# IR_LED.net
KiCad netlist of a schematic drawn in EAGLE
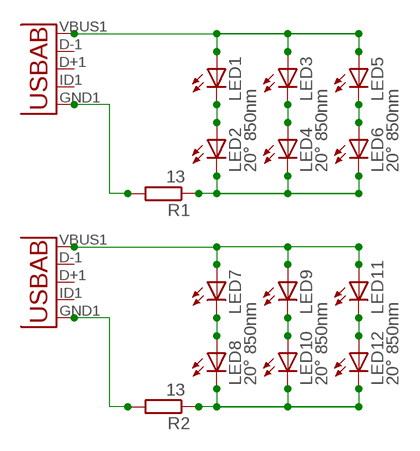
[diagram p0: schematic, sheet 1]

(export (version "E")
  (design (tool "Eeschema 10.0.6"))
  (components
    (comp (ref "LED1")
      (value "LED5MM")
      (footprint "eagle-import:LED5MM")
      (libsource (lib "eagle-import") (part "LED5MM"))
    )
    (comp (ref "LED2")
      (value "20° 850nm")
      (footprint "eagle-import:LED5MM")
      (libsource (lib "eagle-import") (part "LED5MM"))
    )
    (comp (ref "LED3")
      (value "LED5MM")
      (footprint "eagle-import:LED5MM")
      (libsource (lib "eagle-import") (part "LED5MM"))
    )
    (comp (ref "LED4")
      (value "20° 850nm")
      (footprint "eagle-import:LED5MM")
      (libsource (lib "eagle-import") (part "LED5MM"))
    )
    (comp (ref "LED5")
      (value "LED5MM")
      (footprint "eagle-import:LED5MM")
      (libsource (lib "eagle-import") (part "LED5MM"))
    )
    (comp (ref "LED6")
      (value "20° 850nm")
      (footprint "eagle-import:LED5MM")
      (libsource (lib "eagle-import") (part "LED5MM"))
    )
    (comp (ref "LED7")
      (value "LED5MM")
      (footprint "eagle-import:LED5MM")
      (libsource (lib "eagle-import") (part "LED5MM"))
    )
    (comp (ref "LED8")
      (value "20° 850nm")
      (footprint "eagle-import:LED5MM")
      (libsource (lib "eagle-import") (part "LED5MM"))
    )
    (comp (ref "LED9")
      (value "LED5MM")
      (footprint "eagle-import:LED5MM")
      (libsource (lib "eagle-import") (part "LED5MM"))
    )
    (comp (ref "LED10")
      (value "20° 850nm")
      (footprint "eagle-import:LED5MM")
      (libsource (lib "eagle-import") (part "LED5MM"))
    )
    (comp (ref "LED11")
      (value "LED5MM")
      (footprint "eagle-import:LED5MM")
      (libsource (lib "eagle-import") (part "LED5MM"))
    )
    (comp (ref "LED12")
      (value "20° 850nm")
      (footprint "eagle-import:LED5MM")
      (libsource (lib "eagle-import") (part "LED5MM"))
    )
    (comp (ref "R1")
      (value "13")
      (footprint "eagle-import:0204_7")
      (libsource (lib "eagle-import") (part "R-EU_0204/7"))
    )
    (comp (ref "R2")
      (value "13")
      (footprint "eagle-import:0204_7")
      (libsource (lib "eagle-import") (part "R-EU_0204/7"))
    )
    (comp (ref "U1")
      (value "USB\"\"")
      (footprint "eagle-import:USB-MICRO-SMD")
      (libsource (lib "eagle-import") (part "USB{dblquote}{dblquote}"))
    )
    (comp (ref "U2")
      (value "USB\"\"")
      (footprint "eagle-import:USB-MICRO-SMD")
      (libsource (lib "eagle-import") (part "USB{dblquote}{dblquote}"))
    )
  )
  (nets
    (net (code "1") (name "Net-(LED1-C)") (class "Default")
      (node (ref "LED1") (pin "K") (pinfunction "C_K") (pintype "passive"))
      (node (ref "LED2") (pin "A") (pinfunction "A_A") (pintype "passive"))
    )
    (net (code "2") (name "Net-(LED2-C)") (class "Default")
      (node (ref "LED2") (pin "K") (pinfunction "C_K") (pintype "passive"))
      (node (ref "LED4") (pin "K") (pinfunction "C_K") (pintype "passive"))
      (node (ref "LED6") (pin "K") (pinfunction "C_K") (pintype "passive"))
      (node (ref "R1") (pin "1") (pinfunction "1_1") (pintype "passive"))
    )
    (net (code "3") (name "Net-(LED3-C)") (class "Default")
      (node (ref "LED3") (pin "K") (pinfunction "C_K") (pintype "passive"))
      (node (ref "LED4") (pin "A") (pinfunction "A_A") (pintype "passive"))
    )
    (net (code "4") (name "Net-(LED5-C)") (class "Default")
      (node (ref "LED5") (pin "K") (pinfunction "C_K") (pintype "passive"))
      (node (ref "LED6") (pin "A") (pinfunction "A_A") (pintype "passive"))
    )
    (net (code "5") (name "Net-(LED7-C)") (class "Default")
      (node (ref "LED7") (pin "K") (pinfunction "C_K") (pintype "passive"))
      (node (ref "LED8") (pin "A") (pinfunction "A_A") (pintype "passive"))
    )
    (net (code "6") (name "Net-(LED9-C)") (class "Default")
      (node (ref "LED10") (pin "A") (pinfunction "A_A") (pintype "passive"))
      (node (ref "LED9") (pin "K") (pinfunction "C_K") (pintype "passive"))
    )
    (net (code "7") (name "Net-(LED10-C)") (class "Default")
      (node (ref "LED10") (pin "K") (pinfunction "C_K") (pintype "passive"))
      (node (ref "LED12") (pin "K") (pinfunction "C_K") (pintype "passive"))
      (node (ref "LED8") (pin "K") (pinfunction "C_K") (pintype "passive"))
      (node (ref "R2") (pin "1") (pinfunction "1_1") (pintype "passive"))
    )
    (net (code "8") (name "Net-(LED11-C)") (class "Default")
      (node (ref "LED11") (pin "K") (pinfunction "C_K") (pintype "passive"))
      (node (ref "LED12") (pin "A") (pinfunction "A_A") (pintype "passive"))
    )
    (net (code "9") (name "Net-(U1-GND)") (class "Default")
      (node (ref "R1") (pin "2") (pinfunction "2_2") (pintype "passive"))
      (node (ref "U1") (pin "GND1") (pinfunction "GND_GND1") (pintype "bidirectional"))
    )
    (net (code "10") (name "Net-(U1-VBUS)") (class "Default")
      (node (ref "LED1") (pin "A") (pinfunction "A_A") (pintype "passive"))
      (node (ref "LED3") (pin "A") (pinfunction "A_A") (pintype "passive"))
      (node (ref "LED5") (pin "A") (pinfunction "A_A") (pintype "passive"))
      (node (ref "U1") (pin "VBUS1") (pinfunction "VBUS_VBUS1") (pintype "bidirectional"))
    )
    (net (code "11") (name "Net-(U2-GND)") (class "Default")
      (node (ref "R2") (pin "2") (pinfunction "2_2") (pintype "passive"))
      (node (ref "U2") (pin "GND1") (pinfunction "GND_GND1") (pintype "bidirectional"))
    )
    (net (code "12") (name "Net-(U2-VBUS)") (class "Default")
      (node (ref "LED11") (pin "A") (pinfunction "A_A") (pintype "passive"))
      (node (ref "LED7") (pin "A") (pinfunction "A_A") (pintype "passive"))
      (node (ref "LED9") (pin "A") (pinfunction "A_A") (pintype "passive"))
      (node (ref "U2") (pin "VBUS1") (pinfunction "VBUS_VBUS1") (pintype "bidirectional"))
    )
    (net (code "13") (name "unconnected-(U1-D+-PadD+1)") (class "Default")
      (node (ref "U1") (pin "D+1") (pinfunction "D+_D+1") (pintype "bidirectional"))
    )
    (net (code "14") (name "unconnected-(U1-D--PadD-1)") (class "Default")
      (node (ref "U1") (pin "D-1") (pinfunction "D-_D-1") (pintype "bidirectional"))
    )
    (net (code "15") (name "unconnected-(U1-USBID-PadID1)") (class "Default")
      (node (ref "U1") (pin "ID1") (pinfunction "USBID_ID1") (pintype "bidirectional"))
    )
    (net (code "16") (name "unconnected-(U2-D+-PadD+1)") (class "Default")
      (node (ref "U2") (pin "D+1") (pinfunction "D+_D+1") (pintype "bidirectional"))
    )
    (net (code "17") (name "unconnected-(U2-D--PadD-1)") (class "Default")
      (node (ref "U2") (pin "D-1") (pinfunction "D-_D-1") (pintype "bidirectional"))
    )
    (net (code "18") (name "unconnected-(U2-USBID-PadID1)") (class "Default")
      (node (ref "U2") (pin "ID1") (pinfunction "USBID_ID1") (pintype "bidirectional"))
    )
  )
)
